# 21_Peripherals.net
KiCad netlist of a schematic drawn in Altium Designer
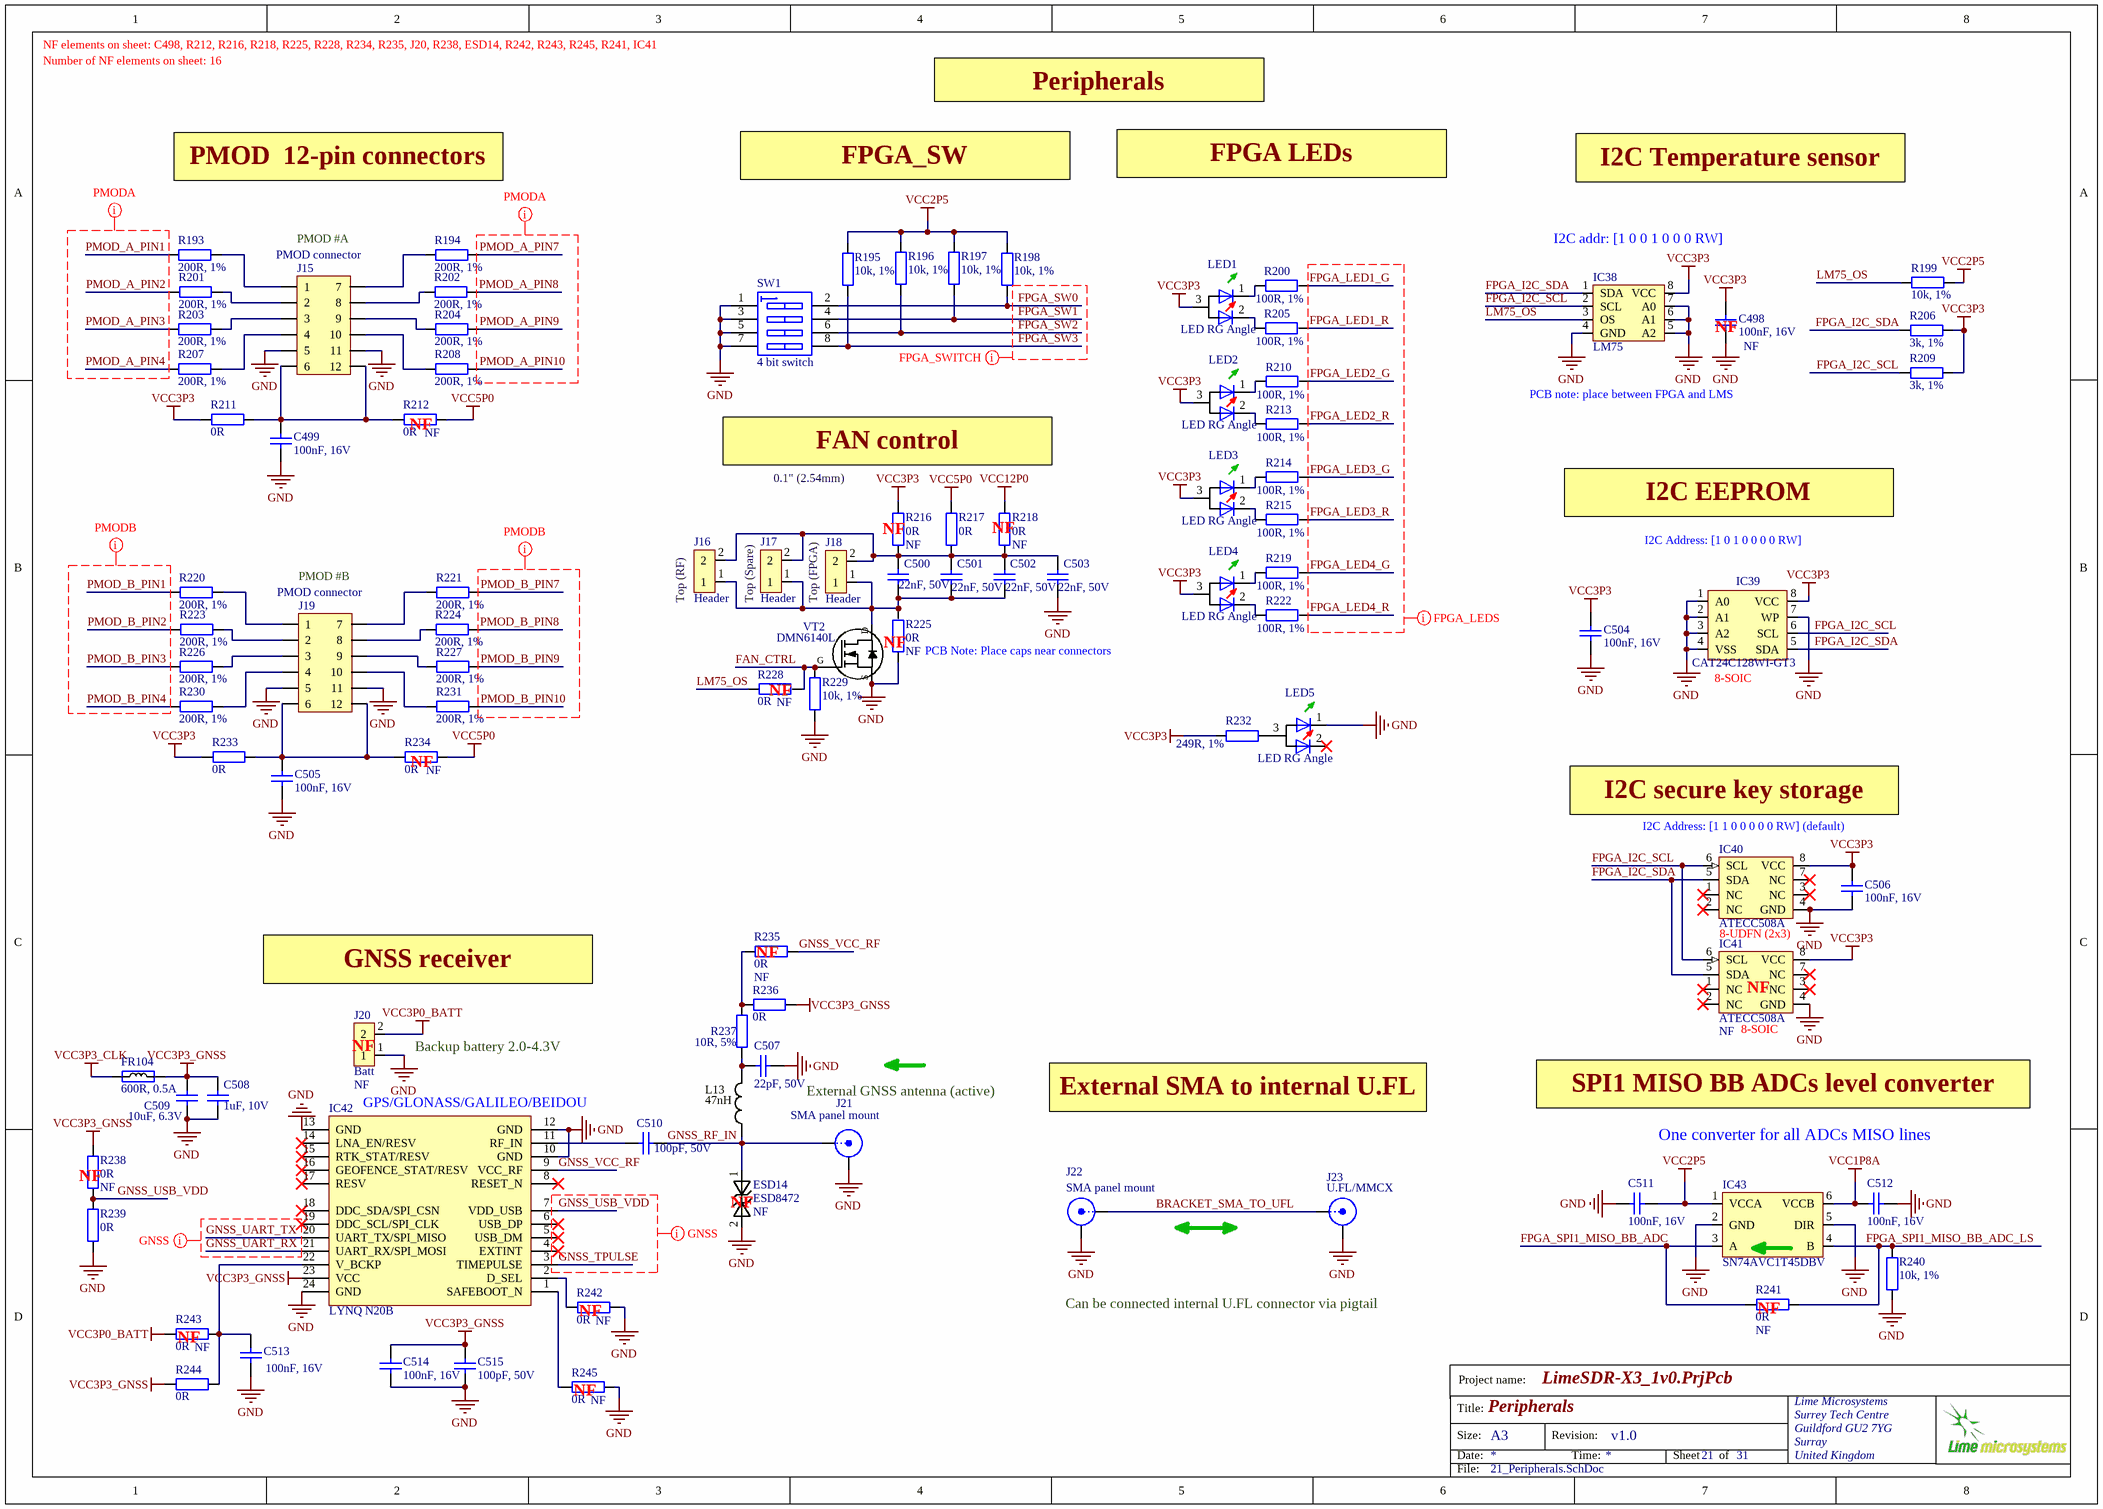
[diagram p0: 21_Peripherals.SchDoc]

(export (version "E")
  (design (tool "Eeschema 10.0.6"))
  (components
    (comp (ref "C498")
      (value "100nF, 16V")
      (footprint "CAP0402")
      (fields
        (field (name "TOLERANCE") "10 %")
        (field (name "MANUFACTURER") "Murata Electronics")
        (field (name "ASSEMBLY INFO") "NF")
      )
      (libsource (lib "") (part "Cap_0603_3"))
    )
    (comp (ref "C499")
      (value "100nF, 16V")
      (footprint "CAP0402")
      (fields
        (field (name "TOLERANCE") "10 %")
        (field (name "MANUFACTURER") "Murata Electronics")
        (field (name "MANUFACTURER PART NUMBER") "GRM155R71C104KA88D")
      )
      (libsource (lib "") (part "Cap_0603_2"))
    )
    (comp (ref "C500")
      (value "22nF, 50V")
      (footprint "CAP0402")
      (fields (field (name "TOLERANCE") "±10%") (field (name "MANUFACTURER") "Kemet"))
      (libsource (lib "") (part "Cap_0402_2"))
    )
    (comp (ref "C501")
      (value "22nF, 50V")
      (footprint "CAP0402")
      (fields (field (name "TOLERANCE") "±10%") (field (name "MANUFACTURER") "Kemet"))
      (libsource (lib "LimeMicroAltiumLib_schLib") (part "Cap_0402"))
    )
    (comp (ref "C502")
      (value "22nF, 50V")
      (footprint "CAP0402")
      (fields (field (name "TOLERANCE") "±10%") (field (name "MANUFACTURER") "Kemet"))
      (libsource (lib "LimeMicroAltiumLib_schLib") (part "Cap_0402"))
    )
    (comp (ref "C503")
      (value "22nF, 50V")
      (footprint "CAP0402")
      (fields (field (name "TOLERANCE") "±10%") (field (name "MANUFACTURER") "Kemet"))
      (libsource (lib "LimeMicroAltiumLib_schLib") (part "Cap_0402"))
    )
    (comp (ref "C504")
      (value "100nF, 16V")
      (footprint "CAP0402")
      (fields (field (name "TOLERANCE") "10 %") (field (name "MANUFACTURER") "Murata Electronics"))
      (libsource (lib "LimeFPGAboard_schLib") (part "Cap_0603"))
    )
    (comp (ref "C505")
      (value "100nF, 16V")
      (footprint "CAP0402")
      (fields
        (field (name "TOLERANCE") "10 %")
        (field (name "MANUFACTURER") "Murata Electronics")
        (field (name "MANUFACTURER PART NUMBER") "GRM155R71C104KA88D")
      )
      (libsource (lib "") (part "Cap_0603_2"))
    )
    (comp (ref "C506")
      (value "100nF, 16V")
      (footprint "CAP0402")
      (fields (field (name "TOLERANCE") "10 %") (field (name "MANUFACTURER") "Murata Electronics"))
      (libsource (lib "LimeFPGAboard_schLib") (part "Cap_0603"))
    )
    (comp (ref "C507")
      (value "22pF, 50V")
      (footprint "CAP0402")
      (fields (field (name "TOLERANCE") "±5%") (field (name "MANUFACTURER") "Yageo"))
      (libsource (lib "") (part "Cap_0402_1"))
    )
    (comp (ref "C508")
      (value "1uF, 10V")
      (footprint "CAP0402")
      (description "CAP CER 1UF 10V X5R 0402")
      (fields (field (name "MANUFACTURER") "TDK"))
      (libsource (lib "") (part "Cap_0402_1"))
    )
    (comp (ref "C509")
      (value "10uF, 6.3V")
      (footprint "CAP0603")
      (fields (field (name "TOLERANCE") "±20%") (field (name "MANUFACTURER") "Yageo"))
      (libsource (lib "") (part "Cap_0603_2"))
    )
    (comp (ref "C510")
      (value "100pF, 50V")
      (footprint "CAP0402")
      (fields (field (name "TOLERANCE") "±5%") (field (name "MANUFACTURER") "Yageo"))
      (libsource (lib "") (part "Cap_0402_1"))
    )
    (comp (ref "C511")
      (value "100nF, 16V")
      (footprint "CAP0402")
      (fields (field (name "TOLERANCE") "10 %") (field (name "MANUFACTURER") "Murata Electronics"))
      (libsource (lib "") (part "Cap_0603_1"))
    )
    (comp (ref "C512")
      (value "100nF, 16V")
      (footprint "CAP0402")
      (fields (field (name "TOLERANCE") "10 %") (field (name "MANUFACTURER") "Murata Electronics"))
      (libsource (lib "") (part "Cap_0603_1"))
    )
    (comp (ref "C513")
      (value "100nF, 16V")
      (footprint "CAP0402")
      (fields
        (field (name "TOLERANCE") "10 %")
        (field (name "MANUFACTURER") "Murata Electronics")
        (field (name "MANUFACTURER PART NUMBER") "GRM155R71C104KA88D")
      )
      (libsource (lib "") (part "Cap_0603_2"))
    )
    (comp (ref "C514")
      (value "100nF, 16V")
      (footprint "CAP0402")
      (fields
        (field (name "MANUFACTURER") "Murata Electronics")
        (field (name "TOLERANCE") "10 %")
        (field (name "MANUFACTURER PART NUMBER") "GRM155R71C104KA88D")
      )
      (libsource (lib "") (part "Cap_0402_1"))
    )
    (comp (ref "C515")
      (value "100pF, 50V")
      (footprint "CAP0402")
      (fields (field (name "TOLERANCE") "±5%") (field (name "MANUFACTURER") "Yageo"))
      (libsource (lib "") (part "Cap_0402_1"))
    )
    (comp (ref "ESD14")
      (value "ESD8472")
      (footprint "ESD8472_X3DFN2")
      (fields
        (field (name "MANUFACTURER") "ON Semiconductor")
        (field (name "MANUFACTURER PART NUMBER") "ESD8472MUT5G")
        (field (name "ASSEMBLY INFO") "NF")
      )
      (libsource (lib "LimeMicroAltiumLib_schLib") (part "ESD8472"))
    )
    (comp (ref "FR104")
      (value "600R, 0.5A")
      (footprint "RES0402")
      (fields
        (field (name "MANUFACTURER") "Murata")
        (field (name "TOLERANCE") "25%")
        (field (name "Comment") "Ferrite")
      )
      (libsource (lib "LimeMicroAltiumLib_schLib") (part "Ferrite"))
    )
    (comp (ref "IC38")
      (value "LM75")
      (footprint "HWSON8_LM75")
      (fields (field (name "MANUFACTURER") "NXP Semiconductors"))
      (libsource (lib "LimeMicroAltiumLib_schLib") (part "LM75"))
    )
    (comp (ref "IC39")
      (value "CAT24C128WI-GT3")
      (footprint "SOIC127P600-8DL_v2")
      (fields (field (name "MANUFACTURER") "ON Semiconductor") (field (name "BASE PART NUMBER") "CAT24C128"))
      (libsource (lib "LimeMicroAltiumLib_schLib") (part "24FC64F"))
    )
    (comp (ref "IC40")
      (value "ATECC508A")
      (footprint "ATECC508A_UDFN8")
      (fields (field (name "MANUFACTURER") "Microchip"))
      (libsource (lib "LimeMicroAltiumLib_schLib_r01") (part "ATECC508A_authentication_IC"))
    )
    (comp (ref "IC41")
      (value "ATECC508A")
      (footprint "SOIC127P600-8DL_v2")
      (fields
        (field (name "ASSEMBLY INFO") "NF")
        (field (name "MANUFACTURER") "Microchip Technology")
        (field (name "BASE PART NUMBER") "ATECC508")
      )
      (libsource (lib "") (part "ATECC508A_authentication_IC_1"))
    )
    (comp (ref "IC42")
      (value "LYNQ N20B")
      (footprint "NEO-7M/8M")
      (description "GNSS engine for GPS/QZSS, GLONASS")
      (fields (field (name "MANUFACTURER") "RF channe;"))
      (libsource (lib "LimeMicroAltiumLib_schLib") (part "NEO-M8P_M8M"))
    )
    (comp (ref "IC43")
      (value "SN74AVC1T45DBV")
      (footprint "SOT23-6")
      (fields (field (name "MANUFACTURER") "Texas Instruments"))
      (libsource (lib "LimeMicroAltiumLib_schLib_r01") (part "SN74AVC1T45DBV"))
    )
    (comp (ref "J15")
      (value "PMOD connector")
      (footprint "PMODconn_right_angle_TH")
      (description "Header, 4-Pin, Dual row")
      (fields (field (name "MANUFACTURER") "Sullins Connector Solutions"))
      (libsource (lib "LimeMicroAltiumLib_schLib") (part "PMOD_connector"))
    )
    (comp (ref "J16")
      (value "Header")
      (footprint "HDR_1x2")
      (fields (field (name "MANUFACTURER") "Wurth Electronics"))
      (libsource (lib "") (part "Jumper_1"))
    )
    (comp (ref "J17")
      (value "Header")
      (footprint "HDR_1x2")
      (fields (field (name "MANUFACTURER") "Wurth Electronics"))
      (libsource (lib "") (part "Jumper_1"))
    )
    (comp (ref "J18")
      (value "Header")
      (footprint "HDR_1x2")
      (fields (field (name "MANUFACTURER") "Wurth Electronics"))
      (libsource (lib "") (part "Jumper_1"))
    )
    (comp (ref "J19")
      (value "PMOD connector")
      (footprint "PMODconn_right_angle_TH")
      (description "Header, 4-Pin, Dual row")
      (fields (field (name "MANUFACTURER") "Sullins Connector Solutions"))
      (libsource (lib "LimeMicroAltiumLib_schLib") (part "PMOD_connector"))
    )
    (comp (ref "J20")
      (value "Batt")
      (footprint "HDR_1x2")
      (fields (field (name "ASSEMBLY INFO") "NF") (field (name "MANUFACTURER") "3M"))
      (libsource (lib "LimeFPGAboard_schLib") (part "Jumper"))
    )
    (comp (ref "J21")
      (value "SMA panel mount")
      (footprint "SMA_connector_side")
      (description "CONN SMA JACK STR 50OHM EDGE MNT")
      (fields (field (name "MANUFACTURER") "Linx"))
      (libsource (lib "LimeMicroAltiumLib_schLib") (part "RF_IF_connector"))
    )
    (comp (ref "J22")
      (value "SMA panel mount")
      (footprint "SMA_connector_side")
      (description "CONN SMA JACK STR 50OHM EDGE MNT")
      (fields (field (name "MANUFACTURER") "Linx"))
      (libsource (lib "LimeMicroAltiumLib_schLib") (part "RF_IF_connector"))
    )
    (comp (ref "J23")
      (value "U.FL/MMCX")
      (footprint "MMCX_UFL_conn_u")
      (description "CONN UMC RCPT STR 50 OHM SMD")
      (fields (field (name "MANUFACTURER") "Molex, LLC"))
      (libsource (lib "") (part "RF_IF_connector_1"))
    )
    (comp (ref "L13")
      (value "47nH")
      (footprint "RES0402")
      (fields
        (field (name "MANUFACTURER") "COILCRAFT")
        (field (name "MANUFACTURER PART NUMBER") "0402HP-47NXJLU")
      )
      (libsource (lib "LimeMicroAltiumLib_schLib") (part "Inductor_0603"))
    )
    (comp (ref "LED1")
      (value "LED RG Angle")
      (footprint "LED_RG_RIGHT_ANGLE_v3")
      (fields (field (name "MANUFACTURER") "Stanley Electric"))
      (libsource (lib "LimeMicroAltiumLib_schLib_r03") (part "LED_green_red_right_angle_v2"))
    )
    (comp (ref "LED2")
      (value "LED RG Angle")
      (footprint "LED_RG_RIGHT_ANGLE_v3")
      (fields (field (name "MANUFACTURER") "Stanley Electric"))
      (libsource (lib "LimeMicroAltiumLib_schLib_r03") (part "LED_green_red_right_angle_v2"))
    )
    (comp (ref "LED3")
      (value "LED RG Angle")
      (footprint "LED_RG_RIGHT_ANGLE_v3")
      (fields (field (name "MANUFACTURER") "Stanley Electric"))
      (libsource (lib "LimeMicroAltiumLib_schLib_r03") (part "LED_green_red_right_angle_v2"))
    )
    (comp (ref "LED4")
      (value "LED RG Angle")
      (footprint "LED_RG_RIGHT_ANGLE_v3")
      (fields (field (name "MANUFACTURER") "Stanley Electric"))
      (libsource (lib "LimeMicroAltiumLib_schLib_r03") (part "LED_green_red_right_angle_v2"))
    )
    (comp (ref "LED5")
      (value "LED RG Angle")
      (footprint "LED_RG_RIGHT_ANGLE_v3")
      (fields (field (name "MANUFACTURER") "Stanley Electric"))
      (libsource (lib "LimeMicroAltiumLib_schLib_r03") (part "LED_green_red_right_angle_v2"))
    )
    (comp (ref "R193")
      (value "200R, 1%")
      (footprint "RES0402")
      (fields (field (name "MANUFACTURER") "Yageo") (field (name "TOLERANCE") "1%"))
      (libsource (lib "") (part "Res_0402_1"))
    )
    (comp (ref "R194")
      (value "200R, 1%")
      (footprint "RES0402")
      (fields (field (name "MANUFACTURER") "Yageo") (field (name "TOLERANCE") "1%"))
      (libsource (lib "") (part "Res_0402_1"))
    )
    (comp (ref "R195")
      (value "10k, 1%")
      (footprint "RES0402")
      (fields (field (name "MANUFACTURER") "Yageo") (field (name "TOLERANCE") "±1%"))
      (libsource (lib "") (part "Res_0402_1"))
    )
    (comp (ref "R196")
      (value "10k, 1%")
      (footprint "RES0402")
      (fields (field (name "MANUFACTURER") "Yageo") (field (name "TOLERANCE") "±1%"))
      (libsource (lib "") (part "Res_0402_1"))
    )
    (comp (ref "R197")
      (value "10k, 1%")
      (footprint "RES0402")
      (fields (field (name "MANUFACTURER") "Yageo") (field (name "TOLERANCE") "±1%"))
      (libsource (lib "") (part "Res_0402_1"))
    )
    (comp (ref "R198")
      (value "10k, 1%")
      (footprint "RES0402")
      (fields (field (name "MANUFACTURER") "Yageo") (field (name "TOLERANCE") "±1%"))
      (libsource (lib "") (part "Res_0402_1"))
    )
    (comp (ref "R199")
      (value "10k, 1%")
      (footprint "RES0402")
      (fields (field (name "MANUFACTURER") "Yageo") (field (name "TOLERANCE") "±1%"))
      (libsource (lib "LimeMicroAltiumLib_schLib") (part "Res_0402"))
    )
    (comp (ref "R200")
      (value "100R, 1%")
      (footprint "RES0402")
      (fields (field (name "TOLERANCE") "±1%") (field (name "MANUFACTURER") "Stackpole Electronics Inc."))
      (libsource (lib "LimeMicroAltiumLib_schLib") (part "Res_0402"))
    )
    (comp (ref "R201")
      (value "200R, 1%")
      (footprint "RES0402")
      (fields (field (name "MANUFACTURER") "Yageo") (field (name "TOLERANCE") "1%"))
      (libsource (lib "") (part "Res_0402_1"))
    )
    (comp (ref "R202")
      (value "200R, 1%")
      (footprint "RES0402")
      (fields (field (name "MANUFACTURER") "Yageo") (field (name "TOLERANCE") "1%"))
      (libsource (lib "") (part "Res_0402_1"))
    )
    (comp (ref "R203")
      (value "200R, 1%")
      (footprint "RES0402")
      (fields (field (name "MANUFACTURER") "Yageo") (field (name "TOLERANCE") "1%"))
      (libsource (lib "") (part "Res_0402_1"))
    )
    (comp (ref "R204")
      (value "200R, 1%")
      (footprint "RES0402")
      (fields (field (name "MANUFACTURER") "Yageo") (field (name "TOLERANCE") "1%"))
      (libsource (lib "") (part "Res_0402_1"))
    )
    (comp (ref "R205")
      (value "100R, 1%")
      (footprint "RES0402")
      (fields (field (name "TOLERANCE") "±1%") (field (name "MANUFACTURER") "Stackpole Electronics Inc."))
      (libsource (lib "LimeMicroAltiumLib_schLib") (part "Res_0402"))
    )
    (comp (ref "R206")
      (value "3k, 1%")
      (footprint "RES0402")
      (fields (field (name "TOLERANCE") "±1%") (field (name "MANUFACTURER") "Vishay Dale"))
      (libsource (lib "LimeMicroAltiumLib_schLib") (part "Res_0402"))
    )
    (comp (ref "R207")
      (value "200R, 1%")
      (footprint "RES0402")
      (fields (field (name "MANUFACTURER") "Yageo") (field (name "TOLERANCE") "1%"))
      (libsource (lib "") (part "Res_0402_1"))
    )
    (comp (ref "R208")
      (value "200R, 1%")
      (footprint "RES0402")
      (fields (field (name "MANUFACTURER") "Yageo") (field (name "TOLERANCE") "1%"))
      (libsource (lib "") (part "Res_0402_1"))
    )
    (comp (ref "R209")
      (value "3k, 1%")
      (footprint "RES0402")
      (fields (field (name "TOLERANCE") "±1%") (field (name "MANUFACTURER") "Vishay Dale"))
      (libsource (lib "LimeMicroAltiumLib_schLib") (part "Res_0402"))
    )
    (comp (ref "R210")
      (value "100R, 1%")
      (footprint "RES0402")
      (fields (field (name "TOLERANCE") "±1%") (field (name "MANUFACTURER") "Stackpole Electronics Inc."))
      (libsource (lib "LimeMicroAltiumLib_schLib") (part "Res_0402"))
    )
    (comp (ref "R211")
      (value "0R")
      (footprint "RES0402")
      (fields (field (name "MANUFACTURER") "Yageo"))
      (libsource (lib "") (part "Res_0402_1"))
    )
    (comp (ref "R212")
      (value "0R")
      (footprint "RES0402")
      (fields (field (name "MANUFACTURER") "Yageo") (field (name "ASSEMBLY INFO") "NF"))
      (libsource (lib "") (part "Res_0402_1"))
    )
    (comp (ref "R213")
      (value "100R, 1%")
      (footprint "RES0402")
      (fields (field (name "TOLERANCE") "±1%") (field (name "MANUFACTURER") "Stackpole Electronics Inc."))
      (libsource (lib "LimeMicroAltiumLib_schLib") (part "Res_0402"))
    )
    (comp (ref "R214")
      (value "100R, 1%")
      (footprint "RES0402")
      (fields (field (name "TOLERANCE") "±1%") (field (name "MANUFACTURER") "Stackpole Electronics Inc."))
      (libsource (lib "LimeMicroAltiumLib_schLib") (part "Res_0402"))
    )
    (comp (ref "R215")
      (value "100R, 1%")
      (footprint "RES0402")
      (fields (field (name "TOLERANCE") "±1%") (field (name "MANUFACTURER") "Stackpole Electronics Inc."))
      (libsource (lib "LimeMicroAltiumLib_schLib") (part "Res_0402"))
    )
    (comp (ref "R216")
      (value "0R")
      (footprint "RES0402")
      (fields
        (field (name "ASSEMBLY INFO") "NF")
        (field (name "MANUFACTURER") "Yageo")
        (field (name "TOLERANCE") "Jumper")
      )
      (libsource (lib "LimeMicroAltiumLib_schLib") (part "Res_0402"))
    )
    (comp (ref "R217")
      (value "0R")
      (footprint "RES0402")
      (fields (field (name "MANUFACTURER") "Yageo") (field (name "TOLERANCE") "Jumper"))
      (libsource (lib "LimeMicroAltiumLib_schLib") (part "Res_0402"))
    )
    (comp (ref "R218")
      (value "0R")
      (footprint "RES0402")
      (fields
        (field (name "ASSEMBLY INFO") "NF")
        (field (name "MANUFACTURER") "Yageo")
        (field (name "TOLERANCE") "Jumper")
      )
      (libsource (lib "LimeMicroAltiumLib_schLib") (part "Res_0402"))
    )
    (comp (ref "R219")
      (value "100R, 1%")
      (footprint "RES0402")
      (fields (field (name "TOLERANCE") "±1%") (field (name "MANUFACTURER") "Stackpole Electronics Inc."))
      (libsource (lib "LimeMicroAltiumLib_schLib") (part "Res_0402"))
    )
    (comp (ref "R220")
      (value "200R, 1%")
      (footprint "RES0402")
      (fields (field (name "MANUFACTURER") "Yageo") (field (name "TOLERANCE") "1%"))
      (libsource (lib "") (part "Res_0402_1"))
    )
    (comp (ref "R221")
      (value "200R, 1%")
      (footprint "RES0402")
      (fields (field (name "MANUFACTURER") "Yageo") (field (name "TOLERANCE") "1%"))
      (libsource (lib "") (part "Res_0402_1"))
    )
    (comp (ref "R222")
      (value "100R, 1%")
      (footprint "RES0402")
      (fields (field (name "TOLERANCE") "±1%") (field (name "MANUFACTURER") "Stackpole Electronics Inc."))
      (libsource (lib "LimeMicroAltiumLib_schLib") (part "Res_0402"))
    )
    (comp (ref "R223")
      (value "200R, 1%")
      (footprint "RES0402")
      (fields (field (name "MANUFACTURER") "Yageo") (field (name "TOLERANCE") "1%"))
      (libsource (lib "") (part "Res_0402_1"))
    )
    (comp (ref "R224")
      (value "200R, 1%")
      (footprint "RES0402")
      (fields (field (name "MANUFACTURER") "Yageo") (field (name "TOLERANCE") "1%"))
      (libsource (lib "") (part "Res_0402_1"))
    )
    (comp (ref "R225")
      (value "0R")
      (footprint "RES0402")
      (fields
        (field (name "ASSEMBLY INFO") "NF")
        (field (name "MANUFACTURER") "Yageo")
        (field (name "TOLERANCE") "Jumper")
      )
      (libsource (lib "LimeMicroAltiumLib_schLib") (part "Res_0402"))
    )
    (comp (ref "R226")
      (value "200R, 1%")
      (footprint "RES0402")
      (fields (field (name "MANUFACTURER") "Yageo") (field (name "TOLERANCE") "1%"))
      (libsource (lib "") (part "Res_0402_1"))
    )
    (comp (ref "R227")
      (value "200R, 1%")
      (footprint "RES0402")
      (fields (field (name "MANUFACTURER") "Yageo") (field (name "TOLERANCE") "1%"))
      (libsource (lib "") (part "Res_0402_1"))
    )
    (comp (ref "R228")
      (value "0R")
      (footprint "RES0402")
      (fields (field (name "MANUFACTURER") "Yageo") (field (name "ASSEMBLY INFO") "NF"))
      (libsource (lib "LimeFPGAboard_schLib") (part "Res_0402"))
    )
    (comp (ref "R229")
      (value "10k, 1%")
      (footprint "RES0402")
      (fields (field (name "MANUFACTURER") "Yageo") (field (name "TOLERANCE") "±1%"))
      (libsource (lib "LimeMicroAltiumLib_schLib") (part "Res_0402"))
    )
    (comp (ref "R230")
      (value "200R, 1%")
      (footprint "RES0402")
      (fields (field (name "MANUFACTURER") "Yageo") (field (name "TOLERANCE") "1%"))
      (libsource (lib "") (part "Res_0402_1"))
    )
    (comp (ref "R231")
      (value "200R, 1%")
      (footprint "RES0402")
      (fields (field (name "MANUFACTURER") "Yageo") (field (name "TOLERANCE") "1%"))
      (libsource (lib "") (part "Res_0402_1"))
    )
    (comp (ref "R232")
      (value "249R, 1%")
      (footprint "RES0402")
      (fields (field (name "MANUFACTURER") "Stackpole Electronics Inc") (field (name "TOLERANCE") "±1%"))
      (libsource (lib "LimeMicroAltiumLib_schLib") (part "Res_0402"))
    )
    (comp (ref "R233")
      (value "0R")
      (footprint "RES0402")
      (fields (field (name "MANUFACTURER") "Yageo"))
      (libsource (lib "") (part "Res_0402_1"))
    )
    (comp (ref "R234")
      (value "0R")
      (footprint "RES0402")
      (fields (field (name "MANUFACTURER") "Yageo") (field (name "ASSEMBLY INFO") "NF"))
      (libsource (lib "") (part "Res_0402_1"))
    )
    (comp (ref "R235")
      (value "0R")
      (footprint "RES0402")
      (fields
        (field (name "ASSEMBLY INFO") "NF")
        (field (name "MANUFACTURER") "Yageo")
        (field (name "TOLERANCE") "Jumper")
      )
      (libsource (lib "") (part "Res_0402_1"))
    )
    (comp (ref "R236")
      (value "0R")
      (footprint "RES0402")
      (fields (field (name "MANUFACTURER") "Yageo") (field (name "TOLERANCE") "Jumper"))
      (libsource (lib "") (part "Res_0402_1"))
    )
    (comp (ref "R237")
      (value "10R, 5%")
      (footprint "RES0402")
      (fields (field (name "TOLERANCE") "±5%") (field (name "MANUFACTURER") "Yageo"))
      (libsource (lib "") (part "Res_0402_1"))
    )
    (comp (ref "R238")
      (value "0R")
      (footprint "RES0402")
      (fields
        (field (name "ASSEMBLY INFO") "NF")
        (field (name "MANUFACTURER") "Yageo")
        (field (name "TOLERANCE") "Jumper")
      )
      (libsource (lib "") (part "Res_0402_1"))
    )
    (comp (ref "R239")
      (value "0R")
      (footprint "RES0402")
      (fields (field (name "MANUFACTURER") "Yageo") (field (name "TOLERANCE") "Jumper"))
      (libsource (lib "") (part "Res_0402_1"))
    )
    (comp (ref "R240")
      (value "10k, 1%")
      (footprint "RES0402")
      (fields (field (name "MANUFACTURER") "Yageo") (field (name "TOLERANCE") "±1%"))
      (libsource (lib "LimeMicroAltiumLib_schLib") (part "Res_0402"))
    )
    (comp (ref "R241")
      (value "0R")
      (footprint "RES0402")
      (fields
        (field (name "ASSEMBLY INFO") "NF")
        (field (name "MANUFACTURER") "Yageo")
        (field (name "TOLERANCE") "Jumper")
      )
      (libsource (lib "LimeMicroAltiumLib_schLib") (part "Res_0402"))
    )
    (comp (ref "R242")
      (value "0R")
      (footprint "RES0402")
      (fields
        (field (name "ASSEMBLY INFO") "NF")
        (field (name "MANUFACTURER") "Yageo")
        (field (name "TOLERANCE") "Jumper")
      )
      (libsource (lib "") (part "Res_0402_1"))
    )
    (comp (ref "R243")
      (value "0R")
      (footprint "RES0402")
      (fields
        (field (name "ASSEMBLY INFO") "NF")
        (field (name "MANUFACTURER") "Yageo")
        (field (name "TOLERANCE") "Jumper")
      )
      (libsource (lib "") (part "Res_0402_1"))
    )
    (comp (ref "R244")
      (value "0R")
      (footprint "RES0402")
      (fields (field (name "MANUFACTURER") "Yageo") (field (name "TOLERANCE") "Jumper"))
      (libsource (lib "") (part "Res_0402_1"))
    )
    (comp (ref "R245")
      (value "0R")
      (footprint "RES0402")
      (fields
        (field (name "ASSEMBLY INFO") "NF")
        (field (name "MANUFACTURER") "Yageo")
        (field (name "TOLERANCE") "Jumper")
      )
      (libsource (lib "") (part "Res_0402_1"))
    )
    (comp (ref "SW1")
      (value "4 bit switch")
      (footprint "DS02C-254-1L-04BE_DIP_SWITCH_4PIN")
      (fields (field (name "MANUFACTURER") "CUI Devices"))
      (libsource (lib "LimeMicroAltiumLib_schLib_r03") (part "SW_SM_4bit_v2"))
    )
    (comp (ref "VT2")
      (value "DMN6140L")
      (footprint "SOT23-3")
      (description "NDS331N")
      (fields
        (field (name "MANUFACTURER PART NUMBER") "DMN6140L-13")
        (field (name "MANUFACTURER") "Diodes Incorporated")
      )
      (libsource (lib "LimeFPGAboard_schLib") (part "NDS331N"))
    )
  )
  (nets
    (net (code "1") (name "/BRACKET_SMA_TO_UFL") (class "Default")
      (node (ref "J22") (pin "1") (pinfunction "X_1") (pintype "passive"))
      (node (ref "J23") (pin "1") (pinfunction "X_1") (pintype "passive"))
    )
    (net (code "2") (name "/FAN_CTRL") (class "Default")
      (node (ref "R228") (pin "2") (pinfunction "2_2") (pintype "passive"))
      (node (ref "R229") (pin "1") (pinfunction "1_1") (pintype "passive"))
      (node (ref "VT2") (pin "G") (pinfunction "G_G") (pintype "passive"))
    )
    (net (code "3") (name "/FPGA_I2C_SCL") (class "Default")
      (node (ref "IC38") (pin "2") (pinfunction "SCL_2") (pintype "passive"))
      (node (ref "IC39") (pin "6") (pinfunction "SCL_6") (pintype "passive"))
      (node (ref "IC40") (pin "6") (pinfunction "SCL_6") (pintype "input"))
      (node (ref "IC41") (pin "6") (pinfunction "SCL_6") (pintype "input"))
      (node (ref "R209") (pin "2") (pinfunction "2_2") (pintype "passive"))
    )
    (net (code "4") (name "/FPGA_I2C_SDA") (class "Default")
      (node (ref "IC38") (pin "1") (pinfunction "SDA_1") (pintype "passive"))
      (node (ref "IC39") (pin "5") (pinfunction "SDA_5") (pintype "passive"))
      (node (ref "IC40") (pin "5") (pinfunction "SDA_5") (pintype "bidirectional"))
      (node (ref "IC41") (pin "5") (pinfunction "SDA_5") (pintype "bidirectional"))
      (node (ref "R206") (pin "2") (pinfunction "2_2") (pintype "passive"))
    )
    (net (code "5") (name "/FPGA_LED1_G") (class "Default")
      (node (ref "R200") (pin "2") (pinfunction "2_2") (pintype "passive"))
    )
    (net (code "6") (name "/FPGA_LED1_R") (class "Default")
      (node (ref "R205") (pin "2") (pinfunction "2_2") (pintype "passive"))
    )
    (net (code "7") (name "/FPGA_LED2_G") (class "Default")
      (node (ref "R210") (pin "2") (pinfunction "2_2") (pintype "passive"))
    )
    (net (code "8") (name "/FPGA_LED2_R") (class "Default")
      (node (ref "R213") (pin "2") (pinfunction "2_2") (pintype "passive"))
    )
    (net (code "9") (name "/FPGA_LED3_G") (class "Default")
      (node (ref "R214") (pin "2") (pinfunction "2_2") (pintype "passive"))
    )
    (net (code "10") (name "/FPGA_LED3_R") (class "Default")
      (node (ref "R215") (pin "2") (pinfunction "2_2") (pintype "passive"))
    )
    (net (code "11") (name "/FPGA_LED4_G") (class "Default")
      (node (ref "R219") (pin "2") (pinfunction "2_2") (pintype "passive"))
    )
    (net (code "12") (name "/FPGA_LED4_R") (class "Default")
      (node (ref "R222") (pin "2") (pinfunction "2_2") (pintype "passive"))
    )
    (net (code "13") (name "/FPGA_SPI1_MISO_BB_ADC") (class "Default")
      (node (ref "IC43") (pin "3") (pinfunction "A_3") (pintype "bidirectional"))
      (node (ref "R241") (pin "2") (pinfunction "2_2") (pintype "passive"))
    )
    (net (code "14") (name "/FPGA_SPI1_MISO_BB_ADC_LS") (class "Default")
      (node (ref "IC43") (pin "4") (pinfunction "B_4") (pintype "bidirectional"))
      (node (ref "R240") (pin "2") (pinfunction "2_2") (pintype "passive"))
      (node (ref "R241") (pin "1") (pinfunction "1_1") (pintype "passive"))
    )
    (net (code "15") (name "/FPGA_SW0") (class "Default")
      (node (ref "R198") (pin "2") (pinfunction "2_2") (pintype "passive"))
      (node (ref "SW1") (pin "2") (pinfunction "B1_2") (pintype "passive"))
    )
    (net (code "16") (name "/FPGA_SW1") (class "Default")
      (node (ref "R197") (pin "2") (pinfunction "2_2") (pintype "passive"))
      (node (ref "SW1") (pin "4") (pinfunction "B2_4") (pintype "passive"))
    )
    (net (code "17") (name "/FPGA_SW2") (class "Default")
      (node (ref "R196") (pin "2") (pinfunction "2_2") (pintype "passive"))
      (node (ref "SW1") (pin "6") (pinfunction "B3_6") (pintype "passive"))
    )
    (net (code "18") (name "/FPGA_SW3") (class "Default")
      (node (ref "R195") (pin "2") (pinfunction "2_2") (pintype "passive"))
      (node (ref "SW1") (pin "8") (pinfunction "B4_8") (pintype "passive"))
    )
    (net (code "19") (name "/GNSS_RF_IN") (class "Default")
      (node (ref "C510") (pin "1") (pinfunction "1_1") (pintype "passive"))
      (node (ref "ESD14") (pin "1") (pinfunction "1_1") (pintype "passive"))
      (node (ref "J21") (pin "1") (pinfunction "X_1") (pintype "passive"))
      (node (ref "L13") (pin "1") (pinfunction "1_1") (pintype "passive"))
    )
    (net (code "20") (name "/GNSS_TPULSE") (class "Default")
      (node (ref "IC42") (pin "3") (pinfunction "TIMEPULSE_3") (pintype "passive"))
    )
    (net (code "21") (name "/GNSS_UART_RX") (class "Default")
      (node (ref "IC42") (pin "21") (pinfunction "UART_RX/SPI_MOSI_21") (pintype "passive"))
    )
    (net (code "22") (name "/GNSS_UART_TX") (class "Default")
      (node (ref "IC42") (pin "20") (pinfunction "UART_TX/SPI_MISO_20") (pintype "passive"))
    )
    (net (code "23") (name "/GNSS_USB_VDD") (class "Default")
      (node (ref "IC42") (pin "7") (pinfunction "VDD_USB_7") (pintype "passive"))
      (node (ref "R238") (pin "1") (pinfunction "1_1") (pintype "passive"))
      (node (ref "R239") (pin "1") (pinfunction "1_1") (pintype "passive"))
    )
    (net (code "24") (name "/GNSS_VCC_RF") (class "Default")
      (node (ref "IC42") (pin "9") (pinfunction "VCC_RF_9") (pintype "passive"))
      (node (ref "R235") (pin "2") (pinfunction "2_2") (pintype "passive"))
    )
    (net (code "25") (name "/LM75_OS") (class "Default")
      (node (ref "IC38") (pin "3") (pinfunction "OS_3") (pintype "passive"))
      (node (ref "R199") (pin "1") (pinfunction "1_1") (pintype "passive"))
      (node (ref "R228") (pin "1") (pinfunction "1_1") (pintype "passive"))
    )
    (net (code "26") (name "/PMOD_A_PIN1") (class "Default")
      (node (ref "R193") (pin "1") (pinfunction "1_1") (pintype "passive"))
    )
    (net (code "27") (name "/PMOD_A_PIN2") (class "Default")
      (node (ref "R201") (pin "1") (pinfunction "1_1") (pintype "passive"))
    )
    (net (code "28") (name "/PMOD_A_PIN3") (class "Default")
      (node (ref "R203") (pin "1") (pinfunction "1_1") (pintype "passive"))
    )
    (net (code "29") (name "/PMOD_A_PIN4") (class "Default")
      (node (ref "R207") (pin "1") (pinfunction "1_1") (pintype "passive"))
    )
    (net (code "30") (name "/PMOD_A_PIN7") (class "Default")
      (node (ref "R194") (pin "2") (pinfunction "2_2") (pintype "passive"))
    )
    (net (code "31") (name "/PMOD_A_PIN8") (class "Default")
      (node (ref "R202") (pin "2") (pinfunction "2_2") (pintype "passive"))
    )
    (net (code "32") (name "/PMOD_A_PIN9") (class "Default")
      (node (ref "R204") (pin "2") (pinfunction "2_2") (pintype "passive"))
    )
    (net (code "33") (name "/PMOD_A_PIN10") (class "Default")
      (node (ref "R208") (pin "2") (pinfunction "2_2") (pintype "passive"))
    )
    (net (code "34") (name "/PMOD_B_PIN1") (class "Default")
      (node (ref "R220") (pin "1") (pinfunction "1_1") (pintype "passive"))
    )
    (net (code "35") (name "/PMOD_B_PIN2") (class "Default")
      (node (ref "R223") (pin "1") (pinfunction "1_1") (pintype "passive"))
    )
    (net (code "36") (name "/PMOD_B_PIN3") (class "Default")
      (node (ref "R226") (pin "1") (pinfunction "1_1") (pintype "passive"))
    )
    (net (code "37") (name "/PMOD_B_PIN4") (class "Default")
      (node (ref "R230") (pin "1") (pinfunction "1_1") (pintype "passive"))
    )
    (net (code "38") (name "/PMOD_B_PIN7") (class "Default")
      (node (ref "R221") (pin "2") (pinfunction "2_2") (pintype "passive"))
    )
    (net (code "39") (name "/PMOD_B_PIN8") (class "Default")
      (node (ref "R224") (pin "2") (pinfunction "2_2") (pintype "passive"))
    )
    (net (code "40") (name "/PMOD_B_PIN9") (class "Default")
      (node (ref "R227") (pin "2") (pinfunction "2_2") (pintype "passive"))
    )
    (net (code "41") (name "/PMOD_B_PIN10") (class "Default")
      (node (ref "R231") (pin "2") (pinfunction "2_2") (pintype "passive"))
    )
    (net (code "42") (name "GND") (class "Default")
      (node (ref "C498") (pin "2") (pinfunction "2_2") (pintype "passive"))
      (node (ref "C499") (pin "2") (pinfunction "2_2") (pintype "passive"))
      (node (ref "C503") (pin "2") (pinfunction "2_2") (pintype "passive"))
      (node (ref "C504") (pin "2") (pinfunction "2_2") (pintype "passive"))
      (node (ref "C505") (pin "2") (pinfunction "2_2") (pintype "passive"))
      (node (ref "C506") (pin "2") (pinfunction "2_2") (pintype "passive"))
      (node (ref "C507") (pin "1") (pinfunction "1_1") (pintype "passive"))
      (node (ref "C508") (pin "1") (pinfunction "1_1") (pintype "passive"))
      (node (ref "C509") (pin "1") (pinfunction "1_1") (pintype "passive"))
      (node (ref "C511") (pin "1") (pinfunction "1_1") (pintype "passive"))
      (node (ref "C512") (pin "2") (pinfunction "2_2") (pintype "passive"))
      (node (ref "C513") (pin "2") (pinfunction "2_2") (pintype "passive"))
      (node (ref "C514") (pin "1") (pinfunction "1_1") (pintype "passive"))
      (node (ref "C515") (pin "2") (pinfunction "2_2") (pintype "passive"))
      (node (ref "ESD14") (pin "2") (pinfunction "2_2") (pintype "passive"))
      (node (ref "IC38") (pin "4") (pinfunction "GND_4") (pintype "passive"))
      (node (ref "IC38") (pin "5") (pinfunction "A2_5") (pintype "passive"))
      (node (ref "IC38") (pin "6") (pinfunction "A1_6") (pintype "passive"))
      (node (ref "IC38") (pin "7") (pinfunction "A0_7") (pintype "passive"))
      (node (ref "IC39") (pin "1") (pinfunction "A0_1") (pintype "passive"))
      (node (ref "IC39") (pin "2") (pinfunction "A1_2") (pintype "passive"))
      (node (ref "IC39") (pin "3") (pinfunction "A2_3") (pintype "passive"))
      (node (ref "IC39") (pin "4") (pinfunction "VSS_4") (pintype "passive"))
      (node (ref "IC39") (pin "7") (pinfunction "WP_7") (pintype "passive"))
      (node (ref "IC40") (pin "4") (pinfunction "GND_4") (pintype "passive"))
      (node (ref "IC41") (pin "4") (pinfunction "GND_4") (pintype "passive"))
      (node (ref "IC42") (pin "10") (pinfunction "GND_10") (pintype "passive"))
      (node (ref "IC42") (pin "12") (pinfunction "GND_12") (pintype "passive"))
      (node (ref "IC42") (pin "13") (pinfunction "GND_13") (pintype "passive"))
      (node (ref "IC42") (pin "24") (pinfunction "GND_24") (pintype "passive"))
      (node (ref "IC43") (pin "2") (pinfunction "GND_2") (pintype "passive"))
      (node (ref "IC43") (pin "5") (pinfunction "DIR_5") (pintype "input"))
      (node (ref "J15") (pin "11") (pinfunction "11_11") (pintype "passive"))
      (node (ref "J15") (pin "5") (pinfunction "5_5") (pintype "passive"))
      (node (ref "J19") (pin "11") (pinfunction "11_11") (pintype "passive"))
      (node (ref "J19") (pin "5") (pinfunction "5_5") (pintype "passive"))
      (node (ref "J20") (pin "1") (pinfunction "1_1") (pintype "passive"))
      (node (ref "J21") (pin "2") (pinfunction "Y_2") (pintype "passive"))
      (node (ref "J22") (pin "2") (pinfunction "Y_2") (pintype "passive"))
      (node (ref "J23") (pin "2") (pinfunction "Y_2") (pintype "passive"))
      (node (ref "LED5") (pin "1") (pinfunction "C1_1") (pintype "power_in"))
      (node (ref "R225") (pin "1") (pinfunction "1_1") (pintype "passive"))
      (node (ref "R229") (pin "2") (pinfunction "2_2") (pintype "passive"))
      (node (ref "R239") (pin "2") (pinfunction "2_2") (pintype "passive"))
      (node (ref "R240") (pin "1") (pinfunction "1_1") (pintype "passive"))
      (node (ref "R242") (pin "1") (pinfunction "1_1") (pintype "passive"))
      (node (ref "R245") (pin "1") (pinfunction "1_1") (pintype "passive"))
      (node (ref "SW1") (pin "1") (pinfunction "A1_1") (pintype "passive"))
      (node (ref "SW1") (pin "3") (pinfunction "A2_3") (pintype "passive"))
      (node (ref "SW1") (pin "5") (pinfunction "A3_5") (pintype "passive"))
      (node (ref "SW1") (pin "7") (pinfunction "A4_7") (pintype "passive"))
      (node (ref "VT2") (pin "S") (pinfunction "S_S") (pintype "passive"))
    )
    (net (code "43") (name "Net-(C499-Pad1)") (class "Default")
      (node (ref "C499") (pin "1") (pinfunction "1_1") (pintype "passive"))
      (node (ref "J15") (pin "12") (pinfunction "12_12") (pintype "passive"))
      (node (ref "J15") (pin "6") (pinfunction "6_6") (pintype "passive"))
      (node (ref "R211") (pin "1") (pinfunction "1_1") (pintype "passive"))
      (node (ref "R212") (pin "2") (pinfunction "2_2") (pintype "passive"))
    )
    (net (code "44") (name "Net-(C500-Pad1)") (class "Default")
      (node (ref "C500") (pin "1") (pinfunction "1_1") (pintype "passive"))
      (node (ref "C501") (pin "1") (pinfunction "1_1") (pintype "passive"))
      (node (ref "C502") (pin "1") (pinfunction "1_1") (pintype "passive"))
      (node (ref "C503") (pin "1") (pinfunction "1_1") (pintype "passive"))
      (node (ref "J16") (pin "2") (pinfunction "2_2") (pintype "passive"))
      (node (ref "J17") (pin "2") (pinfunction "2_2") (pintype "passive"))
      (node (ref "J18") (pin "2") (pinfunction "2_2") (pintype "passive"))
      (node (ref "R216") (pin "1") (pinfunction "1_1") (pintype "passive"))
      (node (ref "R217") (pin "1") (pinfunction "1_1") (pintype "passive"))
      (node (ref "R218") (pin "1") (pinfunction "1_1") (pintype "passive"))
    )
    (net (code "45") (name "Net-(C500-Pad2)") (class "Default")
      (node (ref "C500") (pin "2") (pinfunction "2_2") (pintype "passive"))
      (node (ref "C501") (pin "2") (pinfunction "2_2") (pintype "passive"))
      (node (ref "C502") (pin "2") (pinfunction "2_2") (pintype "passive"))
      (node (ref "J16") (pin "1") (pinfunction "1_1") (pintype "passive"))
      (node (ref "J17") (pin "1") (pinfunction "1_1") (pintype "passive"))
      (node (ref "J18") (pin "1") (pinfunction "1_1") (pintype "passive"))
      (node (ref "R225") (pin "2") (pinfunction "2_2") (pintype "passive"))
      (node (ref "VT2") (pin "D") (pinfunction "D_D") (pintype "passive"))
    )
    (net (code "46") (name "Net-(C505-Pad1)") (class "Default")
      (node (ref "C505") (pin "1") (pinfunction "1_1") (pintype "passive"))
      (node (ref "J19") (pin "12") (pinfunction "12_12") (pintype "passive"))
      (node (ref "J19") (pin "6") (pinfunction "6_6") (pintype "passive"))
      (node (ref "R233") (pin "1") (pinfunction "1_1") (pintype "passive"))
      (node (ref "R234") (pin "2") (pinfunction "2_2") (pintype "passive"))
    )
    (net (code "47") (name "Net-(C507-Pad2)") (class "Default")
      (node (ref "C507") (pin "2") (pinfunction "2_2") (pintype "passive"))
      (node (ref "L13") (pin "2") (pinfunction "2_2") (pintype "passive"))
      (node (ref "R237") (pin "2") (pinfunction "2_2") (pintype "passive"))
    )
    (net (code "48") (name "Net-(IC42-D_SEL)") (class "Default")
      (node (ref "IC42") (pin "2") (pinfunction "D_SEL_2") (pintype "passive"))
      (node (ref "R242") (pin "2") (pinfunction "2_2") (pintype "passive"))
    )
    (net (code "49") (name "Net-(IC42-RF_IN)") (class "Default")
      (node (ref "C510") (pin "2") (pinfunction "2_2") (pintype "passive"))
      (node (ref "IC42") (pin "11") (pinfunction "RF_IN_11") (pintype "passive"))
    )
    (net (code "50") (name "Net-(IC42-SAFEBOOT_N)") (class "Default")
      (node (ref "IC42") (pin "1") (pinfunction "SAFEBOOT_N_1") (pintype "passive"))
      (node (ref "R245") (pin "2") (pinfunction "2_2") (pintype "passive"))
    )
    (net (code "51") (name "Net-(IC42-V_BCKP)") (class "Default")
      (node (ref "C513") (pin "1") (pinfunction "1_1") (pintype "passive"))
      (node (ref "IC42") (pin "22") (pinfunction "V_BCKP_22") (pintype "passive"))
      (node (ref "R243") (pin "1") (pinfunction "1_1") (pintype "passive"))
      (node (ref "R244") (pin "1") (pinfunction "1_1") (pintype "passive"))
    )
    (net (code "52") (name "Net-(J15-Pad1)") (class "Default")
      (node (ref "J15") (pin "1") (pinfunction "1_1") (pintype "passive"))
      (node (ref "R193") (pin "2") (pinfunction "2_2") (pintype "passive"))
    )
    (net (code "53") (name "Net-(J15-Pad2)") (class "Default")
      (node (ref "J15") (pin "2") (pinfunction "2_2") (pintype "passive"))
      (node (ref "R201") (pin "2") (pinfunction "2_2") (pintype "passive"))
    )
    (net (code "54") (name "Net-(J15-Pad3)") (class "Default")
      (node (ref "J15") (pin "3") (pinfunction "3_3") (pintype "passive"))
      (node (ref "R203") (pin "2") (pinfunction "2_2") (pintype "passive"))
    )
    (net (code "55") (name "Net-(J15-Pad4)") (class "Default")
      (node (ref "J15") (pin "4") (pinfunction "4_4") (pintype "passive"))
      (node (ref "R207") (pin "2") (pinfunction "2_2") (pintype "passive"))
    )
    (net (code "56") (name "Net-(J15-Pad7)") (class "Default")
      (node (ref "J15") (pin "7") (pinfunction "7_7") (pintype "passive"))
      (node (ref "R194") (pin "1") (pinfunction "1_1") (pintype "passive"))
    )
    (net (code "57") (name "Net-(J15-Pad8)") (class "Default")
      (node (ref "J15") (pin "8") (pinfunction "8_8") (pintype "passive"))
      (node (ref "R202") (pin "1") (pinfunction "1_1") (pintype "passive"))
    )
    (net (code "58") (name "Net-(J15-Pad9)") (class "Default")
      (node (ref "J15") (pin "9") (pinfunction "9_9") (pintype "passive"))
      (node (ref "R204") (pin "1") (pinfunction "1_1") (pintype "passive"))
    )
    (net (code "59") (name "Net-(J15-Pad10)") (class "Default")
      (node (ref "J15") (pin "10") (pinfunction "10_10") (pintype "passive"))
      (node (ref "R208") (pin "1") (pinfunction "1_1") (pintype "passive"))
    )
    (net (code "60") (name "Net-(J19-Pad1)") (class "Default")
      (node (ref "J19") (pin "1") (pinfunction "1_1") (pintype "passive"))
      (node (ref "R220") (pin "2") (pinfunction "2_2") (pintype "passive"))
    )
    (net (code "61") (name "Net-(J19-Pad2)") (class "Default")
      (node (ref "J19") (pin "2") (pinfunction "2_2") (pintype "passive"))
      (node (ref "R223") (pin "2") (pinfunction "2_2") (pintype "passive"))
    )
    (net (code "62") (name "Net-(J19-Pad3)") (class "Default")
      (node (ref "J19") (pin "3") (pinfunction "3_3") (pintype "passive"))
      (node (ref "R226") (pin "2") (pinfunction "2_2") (pintype "passive"))
    )
    (net (code "63") (name "Net-(J19-Pad4)") (class "Default")
      (node (ref "J19") (pin "4") (pinfunction "4_4") (pintype "passive"))
      (node (ref "R230") (pin "2") (pinfunction "2_2") (pintype "passive"))
    )
    (net (code "64") (name "Net-(J19-Pad7)") (class "Default")
      (node (ref "J19") (pin "7") (pinfunction "7_7") (pintype "passive"))
      (node (ref "R221") (pin "1") (pinfunction "1_1") (pintype "passive"))
    )
    (net (code "65") (name "Net-(J19-Pad8)") (class "Default")
      (node (ref "J19") (pin "8") (pinfunction "8_8") (pintype "passive"))
      (node (ref "R224") (pin "1") (pinfunction "1_1") (pintype "passive"))
    )
    (net (code "66") (name "Net-(J19-Pad9)") (class "Default")
      (node (ref "J19") (pin "9") (pinfunction "9_9") (pintype "passive"))
      (node (ref "R227") (pin "1") (pinfunction "1_1") (pintype "passive"))
    )
    (net (code "67") (name "Net-(J19-Pad10)") (class "Default")
      (node (ref "J19") (pin "10") (pinfunction "10_10") (pintype "passive"))
      (node (ref "R231") (pin "1") (pinfunction "1_1") (pintype "passive"))
    )
    (net (code "68") (name "Net-(LED1-C1)") (class "Default")
      (node (ref "LED1") (pin "1") (pinfunction "C1_1") (pintype "power_in"))
      (node (ref "R200") (pin "1") (pinfunction "1_1") (pintype "passive"))
    )
    (net (code "69") (name "Net-(LED1-C2)") (class "Default")
      (node (ref "LED1") (pin "2") (pinfunction "C2_2") (pintype "power_in"))
      (node (ref "R205") (pin "1") (pinfunction "1_1") (pintype "passive"))
    )
    (net (code "70") (name "Net-(LED2-C1)") (class "Default")
      (node (ref "LED2") (pin "1") (pinfunction "C1_1") (pintype "power_in"))
      (node (ref "R210") (pin "1") (pinfunction "1_1") (pintype "passive"))
    )
    (net (code "71") (name "Net-(LED2-C2)") (class "Default")
      (node (ref "LED2") (pin "2") (pinfunction "C2_2") (pintype "power_in"))
      (node (ref "R213") (pin "1") (pinfunction "1_1") (pintype "passive"))
    )
    (net (code "72") (name "Net-(LED3-C1)") (class "Default")
      (node (ref "LED3") (pin "1") (pinfunction "C1_1") (pintype "power_in"))
      (node (ref "R214") (pin "1") (pinfunction "1_1") (pintype "passive"))
    )
    (net (code "73") (name "Net-(LED3-C2)") (class "Default")
      (node (ref "LED3") (pin "2") (pinfunction "C2_2") (pintype "power_in"))
      (node (ref "R215") (pin "1") (pinfunction "1_1") (pintype "passive"))
    )
    (net (code "74") (name "Net-(LED4-C1)") (class "Default")
      (node (ref "LED4") (pin "1") (pinfunction "C1_1") (pintype "power_in"))
      (node (ref "R219") (pin "1") (pinfunction "1_1") (pintype "passive"))
    )
    (net (code "75") (name "Net-(LED4-C2)") (class "Default")
      (node (ref "LED4") (pin "2") (pinfunction "C2_2") (pintype "power_in"))
      (node (ref "R222") (pin "1") (pinfunction "1_1") (pintype "passive"))
    )
    (net (code "76") (name "Net-(LED5-A)") (class "Default")
      (node (ref "LED5") (pin "3") (pinfunction "A_3") (pintype "power_in"))
      (node (ref "R232") (pin "2") (pinfunction "2_2") (pintype "passive"))
    )
    (net (code "77") (name "Net-(R235-Pad1)") (class "Default")
      (node (ref "R235") (pin "1") (pinfunction "1_1") (pintype "passive"))
      (node (ref "R236") (pin "2") (pinfunction "2_2") (pintype "passive"))
      (node (ref "R237") (pin "1") (pinfunction "1_1") (pintype "passive"))
    )
    (net (code "78") (name "VCC1P8A") (class "Default")
      (node (ref "C512") (pin "1") (pinfunction "1_1") (pintype "passive"))
      (node (ref "IC43") (pin "6") (pinfunction "VCCB_6") (pintype "power_in"))
    )
    (net (code "79") (name "VCC2P5") (class "Default")
      (node (ref "C511") (pin "2") (pinfunction "2_2") (pintype "passive"))
      (node (ref "IC43") (pin "1") (pinfunction "VCCA_1") (pintype "power_in"))
      (node (ref "R195") (pin "1") (pinfunction "1_1") (pintype "passive"))
      (node (ref "R196") (pin "1") (pinfunction "1_1") (pintype "passive"))
      (node (ref "R197") (pin "1") (pinfunction "1_1") (pintype "passive"))
      (node (ref "R198") (pin "1") (pinfunction "1_1") (pintype "passive"))
      (node (ref "R199") (pin "2") (pinfunction "2_2") (pintype "passive"))
    )
    (net (code "80") (name "VCC3P0_BATT") (class "Default")
      (node (ref "J20") (pin "2") (pinfunction "2_2") (pintype "passive"))
      (node (ref "R243") (pin "2") (pinfunction "2_2") (pintype "passive"))
    )
    (net (code "81") (name "VCC3P3") (class "Default")
      (node (ref "C498") (pin "1") (pinfunction "1_1") (pintype "passive"))
      (node (ref "C504") (pin "1") (pinfunction "1_1") (pintype "passive"))
      (node (ref "C506") (pin "1") (pinfunction "1_1") (pintype "passive"))
      (node (ref "IC38") (pin "8") (pinfunction "VCC_8") (pintype "passive"))
      (node (ref "IC39") (pin "8") (pinfunction "VCC_8") (pintype "passive"))
      (node (ref "IC40") (pin "8") (pinfunction "VCC_8") (pintype "power_in"))
      (node (ref "IC41") (pin "8") (pinfunction "VCC_8") (pintype "power_in"))
      (node (ref "LED1") (pin "3") (pinfunction "A_3") (pintype "power_in"))
      (node (ref "LED2") (pin "3") (pinfunction "A_3") (pintype "power_in"))
      (node (ref "LED3") (pin "3") (pinfunction "A_3") (pintype "power_in"))
      (node (ref "LED4") (pin "3") (pinfunction "A_3") (pintype "power_in"))
      (node (ref "R206") (pin "1") (pinfunction "1_1") (pintype "passive"))
      (node (ref "R209") (pin "1") (pinfunction "1_1") (pintype "passive"))
      (node (ref "R211") (pin "2") (pinfunction "2_2") (pintype "passive"))
      (node (ref "R216") (pin "2") (pinfunction "2_2") (pintype "passive"))
      (node (ref "R232") (pin "1") (pinfunction "1_1") (pintype "passive"))
      (node (ref "R233") (pin "2") (pinfunction "2_2") (pintype "passive"))
    )
    (net (code "82") (name "VCC3P3_CLK") (class "Default")
      (node (ref "FR104") (pin "1") (pinfunction "1_1") (pintype "passive"))
    )
    (net (code "83") (name "VCC3P3_GNSS") (class "Default")
      (node (ref "C508") (pin "2") (pinfunction "2_2") (pintype "passive"))
      (node (ref "C509") (pin "2") (pinfunction "2_2") (pintype "passive"))
      (node (ref "C514") (pin "2") (pinfunction "2_2") (pintype "passive"))
      (node (ref "C515") (pin "1") (pinfunction "1_1") (pintype "passive"))
      (node (ref "FR104") (pin "2") (pinfunction "2_2") (pintype "passive"))
      (node (ref "IC42") (pin "23") (pinfunction "VCC_23") (pintype "passive"))
      (node (ref "R236") (pin "1") (pinfunction "1_1") (pintype "passive"))
      (node (ref "R238") (pin "2") (pinfunction "2_2") (pintype "passive"))
      (node (ref "R244") (pin "2") (pinfunction "2_2") (pintype "passive"))
    )
    (net (code "84") (name "VCC5P0") (class "Default")
      (node (ref "R212") (pin "1") (pinfunction "1_1") (pintype "passive"))
      (node (ref "R217") (pin "2") (pinfunction "2_2") (pintype "passive"))
      (node (ref "R234") (pin "1") (pinfunction "1_1") (pintype "passive"))
    )
    (net (code "85") (name "VCC12P0") (class "Default")
      (node (ref "R218") (pin "2") (pinfunction "2_2") (pintype "passive"))
    )
    (net (code "86") (name "unconnected-(IC40-NC-Pad1)") (class "Default")
      (node (ref "IC40") (pin "1") (pinfunction "NC_1") (pintype "passive+no_connect"))
    )
    (net (code "87") (name "unconnected-(IC40-NC-Pad2)") (class "Default")
      (node (ref "IC40") (pin "2") (pinfunction "NC_2") (pintype "passive+no_connect"))
    )
    (net (code "88") (name "unconnected-(IC40-NC-Pad3)") (class "Default")
      (node (ref "IC40") (pin "3") (pinfunction "NC_3") (pintype "passive+no_connect"))
    )
    (net (code "89") (name "unconnected-(IC40-NC-Pad7)") (class "Default")
      (node (ref "IC40") (pin "7") (pinfunction "NC_7") (pintype "passive+no_connect"))
    )
    (net (code "90") (name "unconnected-(IC41-NC-Pad1)") (class "Default")
      (node (ref "IC41") (pin "1") (pinfunction "NC_1") (pintype "passive+no_connect"))
    )
    (net (code "91") (name "unconnected-(IC41-NC-Pad2)") (class "Default")
      (node (ref "IC41") (pin "2") (pinfunction "NC_2") (pintype "passive+no_connect"))
    )
    (net (code "92") (name "unconnected-(IC41-NC-Pad3)") (class "Default")
      (node (ref "IC41") (pin "3") (pinfunction "NC_3") (pintype "passive+no_connect"))
    )
    (net (code "93") (name "unconnected-(IC41-NC-Pad7)") (class "Default")
      (node (ref "IC41") (pin "7") (pinfunction "NC_7") (pintype "passive+no_connect"))
    )
    (net (code "94") (name "unconnected-(IC42-DDC_SCL{slash}SPI_CLK-Pad19)") (class "Default")
      (node (ref "IC42") (pin "19") (pinfunction "DDC_SCL/SPI_CLK_19") (pintype "passive+no_connect"))
    )
    (net (code "95") (name "unconnected-(IC42-DDC_SDA{slash}SPI_CSN-Pad18)") (class "Default")
      (node (ref "IC42") (pin "18") (pinfunction "DDC_SDA/SPI_CSN_18") (pintype "passive+no_connect"))
    )
    (net (code "96") (name "unconnected-(IC42-EXTINT-Pad4)") (class "Default")
      (node (ref "IC42") (pin "4") (pinfunction "EXTINT_4") (pintype "passive+no_connect"))
    )
    (net (code "97") (name "unconnected-(IC42-GEOFENCE_STAT{slash}RESV-Pad16)") (class "Default")
      (node (ref "IC42") (pin "16") (pinfunction "GEOFENCE_STAT/RESV_16") (pintype "passive+no_connect"))
    )
    (net (code "98") (name "unconnected-(IC42-LNA_EN{slash}RESV-Pad14)") (class "Default")
      (node (ref "IC42") (pin "14") (pinfunction "LNA_EN/RESV_14") (pintype "passive+no_connect"))
    )
    (net (code "99") (name "unconnected-(IC42-RESET_N-Pad8)") (class "Default")
      (node (ref "IC42") (pin "8") (pinfunction "RESET_N_8") (pintype "passive+no_connect"))
    )
    (net (code "100") (name "unconnected-(IC42-RESV-Pad17)") (class "Default")
      (node (ref "IC42") (pin "17") (pinfunction "RESV_17") (pintype "passive+no_connect"))
    )
    (net (code "101") (name "unconnected-(IC42-RTK_STAT{slash}RESV-Pad15)") (class "Default")
      (node (ref "IC42") (pin "15") (pinfunction "RTK_STAT/RESV_15") (pintype "passive+no_connect"))
    )
    (net (code "102") (name "unconnected-(IC42-USB_DM-Pad5)") (class "Default")
      (node (ref "IC42") (pin "5") (pinfunction "USB_DM_5") (pintype "passive+no_connect"))
    )
    (net (code "103") (name "unconnected-(IC42-USB_DP-Pad6)") (class "Default")
      (node (ref "IC42") (pin "6") (pinfunction "USB_DP_6") (pintype "passive+no_connect"))
    )
    (net (code "104") (name "unconnected-(LED5-C2-Pad2)") (class "Default")
      (node (ref "LED5") (pin "2") (pinfunction "C2_2") (pintype "power_in+no_connect"))
    )
  )
)
